# cape.net
KiCad netlist of a schematic drawn in EAGLE
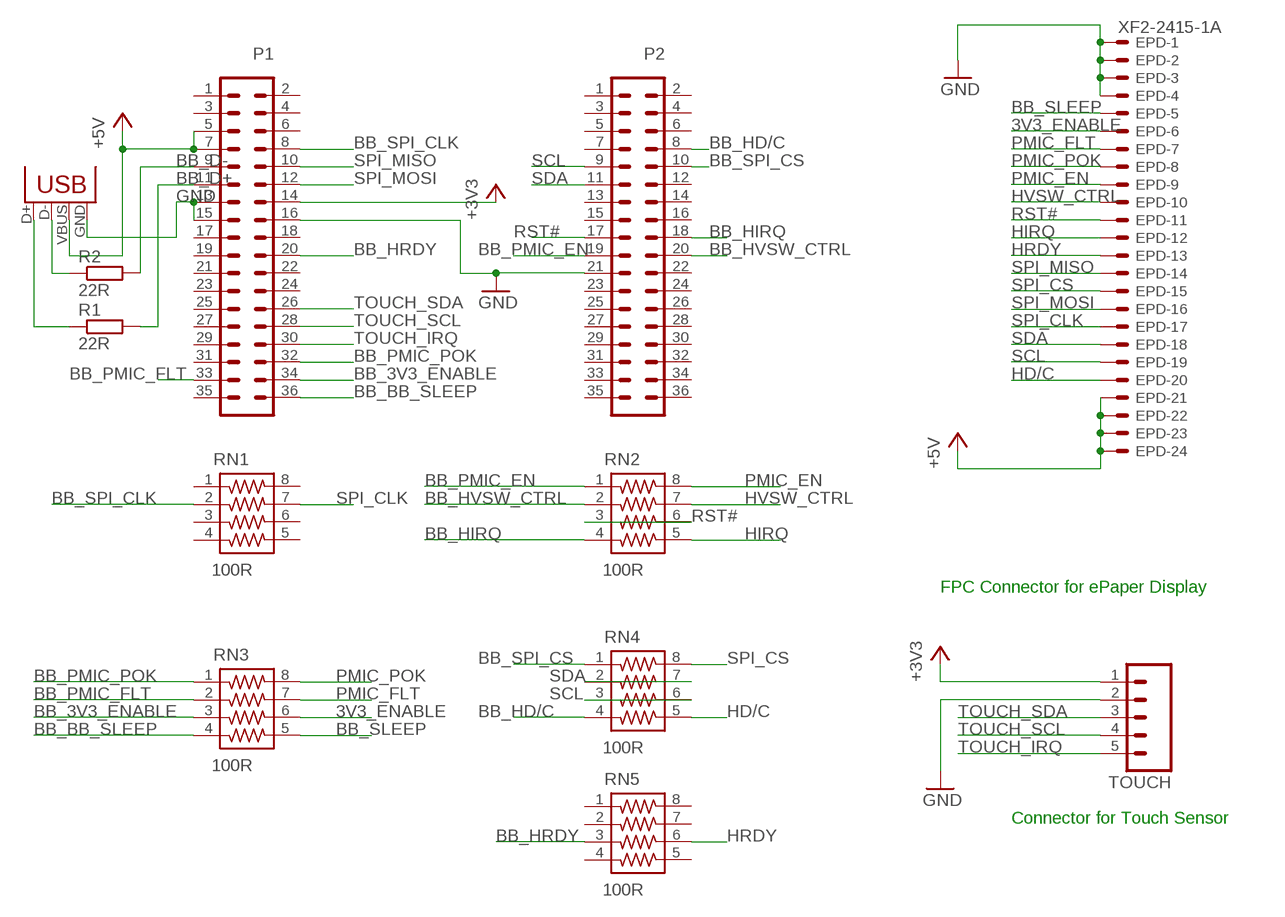
[diagram p0: schematic, sheet 1]

(export (version "E")
  (design (tool "Eeschema 10.0.6"))
  (components
    (comp (ref "EPD")
      (value "XF2-2415-1A")
      (footprint "eagle-import:XF2M-2415-1A")
      (libsource (lib "eagle-import") (part "XF2-24?15-1A"))
    )
    (comp (ref "P1")
      (value "MA18-2")
      (footprint "eagle-import:MA18-2")
      (libsource (lib "eagle-import") (part "MA18-2"))
    )
    (comp (ref "P2")
      (value "MA18-2")
      (footprint "eagle-import:MA18-2")
      (libsource (lib "eagle-import") (part "MA18-2"))
    )
    (comp (ref "R1")
      (value "22R")
      (footprint "eagle-import:R0603")
      (libsource (lib "eagle-import") (part "R-EU_R0603"))
    )
    (comp (ref "R2")
      (value "22R")
      (footprint "eagle-import:R0603")
      (libsource (lib "eagle-import") (part "R-EU_R0603"))
    )
    (comp (ref "RN1")
      (value "100R")
      (footprint "eagle-import:741-8")
      (libsource (lib "eagle-import") (part "741-8"))
    )
    (comp (ref "RN2")
      (value "100R")
      (footprint "eagle-import:741-8")
      (libsource (lib "eagle-import") (part "741-8"))
    )
    (comp (ref "RN3")
      (value "100R")
      (footprint "eagle-import:741-8")
      (libsource (lib "eagle-import") (part "741-8"))
    )
    (comp (ref "RN4")
      (value "100R")
      (footprint "eagle-import:741-8")
      (libsource (lib "eagle-import") (part "741-8"))
    )
    (comp (ref "RN5")
      (value "100R")
      (footprint "eagle-import:741-8")
      (libsource (lib "eagle-import") (part "741-8"))
    )
    (comp (ref "TOUCH")
      (value "M05PTH")
      (footprint "eagle-import:1X05")
      (libsource (lib "eagle-import") (part "M05PTH"))
    )
    (comp (ref "USB")
      (value "USB-A-H")
      (footprint "eagle-import:USB-A-H")
      (libsource (lib "eagle-import") (part "USB-A-H"))
    )
  )
  (nets
    (net (code "1") (name "+3V3") (class "Default")
      (node (ref "P1") (pin "14") (pinfunction "14_14") (pintype "passive"))
      (node (ref "TOUCH") (pin "1") (pinfunction "1_1") (pintype "passive"))
    )
    (net (code "2") (name "+5V") (class "Default")
      (node (ref "EPD") (pin "21") (pinfunction "MS_21") (pintype "passive"))
      (node (ref "EPD") (pin "22") (pinfunction "MS_22") (pintype "passive"))
      (node (ref "EPD") (pin "23") (pinfunction "MS_23") (pintype "passive"))
      (node (ref "EPD") (pin "24") (pinfunction "MS_24") (pintype "passive"))
      (node (ref "P1") (pin "5") (pinfunction "5_5") (pintype "passive"))
      (node (ref "P1") (pin "7") (pinfunction "7_7") (pintype "passive"))
      (node (ref "USB") (pin "VBUS") (pinfunction "VBUS_VBUS") (pintype "bidirectional"))
    )
    (net (code "3") (name "/3V3_ENABLE") (class "Default")
      (node (ref "EPD") (pin "6") (pinfunction "MS_6") (pintype "passive"))
      (node (ref "RN3") (pin "6") (pinfunction "6_6") (pintype "passive"))
    )
    (net (code "4") (name "/BB_3V3_ENABLE") (class "Default")
      (node (ref "P1") (pin "34") (pinfunction "34_34") (pintype "passive"))
      (node (ref "RN3") (pin "3") (pinfunction "3_3") (pintype "passive"))
    )
    (net (code "5") (name "/BB_BB_SLEEP") (class "Default")
      (node (ref "P1") (pin "36") (pinfunction "36_36") (pintype "passive"))
      (node (ref "RN3") (pin "4") (pinfunction "4_4") (pintype "passive"))
    )
    (net (code "6") (name "/BB_D+") (class "Default")
      (node (ref "P1") (pin "11") (pinfunction "11_11") (pintype "passive"))
      (node (ref "R1") (pin "2") (pinfunction "2_2") (pintype "passive"))
    )
    (net (code "7") (name "/BB_D-") (class "Default")
      (node (ref "P1") (pin "9") (pinfunction "9_9") (pintype "passive"))
      (node (ref "R2") (pin "2") (pinfunction "2_2") (pintype "passive"))
    )
    (net (code "8") (name "/BB_HD{slash}C") (class "Default")
      (node (ref "P2") (pin "8") (pinfunction "8_8") (pintype "passive"))
      (node (ref "RN4") (pin "4") (pinfunction "4_4") (pintype "passive"))
    )
    (net (code "9") (name "/BB_HIRQ") (class "Default")
      (node (ref "P2") (pin "18") (pinfunction "18_18") (pintype "passive"))
      (node (ref "RN2") (pin "4") (pinfunction "4_4") (pintype "passive"))
    )
    (net (code "10") (name "/BB_HRDY") (class "Default")
      (node (ref "P1") (pin "20") (pinfunction "20_20") (pintype "passive"))
      (node (ref "RN5") (pin "3") (pinfunction "3_3") (pintype "passive"))
    )
    (net (code "11") (name "/BB_HVSW_CTRL") (class "Default")
      (node (ref "P2") (pin "20") (pinfunction "20_20") (pintype "passive"))
      (node (ref "RN2") (pin "2") (pinfunction "2_2") (pintype "passive"))
    )
    (net (code "12") (name "/BB_PMIC_EN") (class "Default")
      (node (ref "P2") (pin "19") (pinfunction "19_19") (pintype "passive"))
      (node (ref "RN2") (pin "1") (pinfunction "1_1") (pintype "passive"))
    )
    (net (code "13") (name "/BB_PMIC_FLT") (class "Default")
      (node (ref "P1") (pin "33") (pinfunction "33_33") (pintype "passive"))
      (node (ref "RN3") (pin "2") (pinfunction "2_2") (pintype "passive"))
    )
    (net (code "14") (name "/BB_PMIC_POK") (class "Default")
      (node (ref "P1") (pin "32") (pinfunction "32_32") (pintype "passive"))
      (node (ref "RN3") (pin "1") (pinfunction "1_1") (pintype "passive"))
    )
    (net (code "15") (name "/BB_SLEEP") (class "Default")
      (node (ref "EPD") (pin "5") (pinfunction "MS_5") (pintype "passive"))
      (node (ref "RN3") (pin "5") (pinfunction "5_5") (pintype "passive"))
    )
    (net (code "16") (name "/BB_SPI_CLK") (class "Default")
      (node (ref "P1") (pin "8") (pinfunction "8_8") (pintype "passive"))
      (node (ref "RN1") (pin "2") (pinfunction "2_2") (pintype "passive"))
    )
    (net (code "17") (name "/BB_SPI_CS") (class "Default")
      (node (ref "P2") (pin "10") (pinfunction "10_10") (pintype "passive"))
      (node (ref "RN4") (pin "1") (pinfunction "1_1") (pintype "passive"))
    )
    (net (code "18") (name "/HD{slash}C") (class "Default")
      (node (ref "EPD") (pin "20") (pinfunction "MS_20") (pintype "passive"))
      (node (ref "RN4") (pin "5") (pinfunction "5_5") (pintype "passive"))
    )
    (net (code "19") (name "/HIRQ") (class "Default")
      (node (ref "EPD") (pin "12") (pinfunction "MS_12") (pintype "passive"))
      (node (ref "RN2") (pin "5") (pinfunction "5_5") (pintype "passive"))
    )
    (net (code "20") (name "/HRDY") (class "Default")
      (node (ref "EPD") (pin "13") (pinfunction "MS_13") (pintype "passive"))
      (node (ref "RN5") (pin "6") (pinfunction "6_6") (pintype "passive"))
    )
    (net (code "21") (name "/HVSW_CTRL") (class "Default")
      (node (ref "EPD") (pin "10") (pinfunction "MS_10") (pintype "passive"))
      (node (ref "RN2") (pin "7") (pinfunction "7_7") (pintype "passive"))
    )
    (net (code "22") (name "/PMIC_EN") (class "Default")
      (node (ref "EPD") (pin "9") (pinfunction "MS_9") (pintype "passive"))
      (node (ref "RN2") (pin "8") (pinfunction "8_8") (pintype "passive"))
    )
    (net (code "23") (name "/PMIC_FLT") (class "Default")
      (node (ref "EPD") (pin "7") (pinfunction "MS_7") (pintype "passive"))
      (node (ref "RN3") (pin "7") (pinfunction "7_7") (pintype "passive"))
    )
    (net (code "24") (name "/PMIC_POK") (class "Default")
      (node (ref "EPD") (pin "8") (pinfunction "MS_8") (pintype "passive"))
      (node (ref "RN3") (pin "8") (pinfunction "8_8") (pintype "passive"))
    )
    (net (code "25") (name "/RST#") (class "Default")
      (node (ref "EPD") (pin "11") (pinfunction "MS_11") (pintype "passive"))
      (node (ref "P2") (pin "17") (pinfunction "17_17") (pintype "passive"))
      (node (ref "RN2") (pin "3") (pinfunction "3_3") (pintype "passive"))
      (node (ref "RN2") (pin "6") (pinfunction "6_6") (pintype "passive"))
    )
    (net (code "26") (name "/SCL") (class "Default")
      (node (ref "EPD") (pin "19") (pinfunction "MS_19") (pintype "passive"))
      (node (ref "P2") (pin "9") (pinfunction "9_9") (pintype "passive"))
      (node (ref "RN4") (pin "3") (pinfunction "3_3") (pintype "passive"))
      (node (ref "RN4") (pin "6") (pinfunction "6_6") (pintype "passive"))
    )
    (net (code "27") (name "/SDA") (class "Default")
      (node (ref "EPD") (pin "18") (pinfunction "MS_18") (pintype "passive"))
      (node (ref "P2") (pin "11") (pinfunction "11_11") (pintype "passive"))
      (node (ref "RN4") (pin "2") (pinfunction "2_2") (pintype "passive"))
      (node (ref "RN4") (pin "7") (pinfunction "7_7") (pintype "passive"))
    )
    (net (code "28") (name "/SPI_CLK") (class "Default")
      (node (ref "EPD") (pin "17") (pinfunction "MS_17") (pintype "passive"))
      (node (ref "RN1") (pin "7") (pinfunction "7_7") (pintype "passive"))
    )
    (net (code "29") (name "/SPI_CS") (class "Default")
      (node (ref "EPD") (pin "15") (pinfunction "MS_15") (pintype "passive"))
      (node (ref "RN4") (pin "8") (pinfunction "8_8") (pintype "passive"))
    )
    (net (code "30") (name "/SPI_MISO") (class "Default")
      (node (ref "EPD") (pin "14") (pinfunction "MS_14") (pintype "passive"))
      (node (ref "P1") (pin "10") (pinfunction "10_10") (pintype "passive"))
    )
    (net (code "31") (name "/SPI_MOSI") (class "Default")
      (node (ref "EPD") (pin "16") (pinfunction "MS_16") (pintype "passive"))
      (node (ref "P1") (pin "12") (pinfunction "12_12") (pintype "passive"))
    )
    (net (code "32") (name "/TOUCH_IRQ") (class "Default")
      (node (ref "P1") (pin "30") (pinfunction "30_30") (pintype "passive"))
      (node (ref "TOUCH") (pin "5") (pinfunction "5_5") (pintype "passive"))
    )
    (net (code "33") (name "/TOUCH_SCL") (class "Default")
      (node (ref "P1") (pin "28") (pinfunction "28_28") (pintype "passive"))
      (node (ref "TOUCH") (pin "4") (pinfunction "4_4") (pintype "passive"))
    )
    (net (code "34") (name "/TOUCH_SDA") (class "Default")
      (node (ref "P1") (pin "26") (pinfunction "26_26") (pintype "passive"))
      (node (ref "TOUCH") (pin "3") (pinfunction "3_3") (pintype "passive"))
    )
    (net (code "35") (name "GND") (class "Default")
      (node (ref "EPD") (pin "1") (pinfunction "MSV_1") (pintype "passive"))
      (node (ref "EPD") (pin "2") (pinfunction "MS_2") (pintype "passive"))
      (node (ref "EPD") (pin "3") (pinfunction "MS_3") (pintype "passive"))
      (node (ref "EPD") (pin "4") (pinfunction "MS_4") (pintype "passive"))
      (node (ref "P1") (pin "13") (pinfunction "13_13") (pintype "passive"))
      (node (ref "P1") (pin "15") (pinfunction "15_15") (pintype "passive"))
      (node (ref "P1") (pin "16") (pinfunction "16_16") (pintype "passive"))
      (node (ref "P2") (pin "21") (pinfunction "21_21") (pintype "passive"))
      (node (ref "TOUCH") (pin "2") (pinfunction "2_2") (pintype "passive"))
      (node (ref "USB") (pin "GND") (pinfunction "GND_GND") (pintype "bidirectional"))
    )
    (net (code "36") (name "Net-(R1-Pad1)") (class "Default")
      (node (ref "R1") (pin "1") (pinfunction "1_1") (pintype "passive"))
      (node (ref "USB") (pin "D+") (pinfunction "D+_D+") (pintype "bidirectional"))
    )
    (net (code "37") (name "Net-(R2-Pad1)") (class "Default")
      (node (ref "R2") (pin "1") (pinfunction "1_1") (pintype "passive"))
      (node (ref "USB") (pin "D-") (pinfunction "D-_D-") (pintype "bidirectional"))
    )
    (net (code "38") (name "unconnected-(P1-Pad1)") (class "Default")
      (node (ref "P1") (pin "1") (pinfunction "1_1") (pintype "passive"))
    )
    (net (code "39") (name "unconnected-(P1-Pad2)") (class "Default")
      (node (ref "P1") (pin "2") (pinfunction "2_2") (pintype "passive"))
    )
    (net (code "40") (name "unconnected-(P1-Pad3)") (class "Default")
      (node (ref "P1") (pin "3") (pinfunction "3_3") (pintype "passive"))
    )
    (net (code "41") (name "unconnected-(P1-Pad4)") (class "Default")
      (node (ref "P1") (pin "4") (pinfunction "4_4") (pintype "passive"))
    )
    (net (code "42") (name "unconnected-(P1-Pad6)") (class "Default")
      (node (ref "P1") (pin "6") (pinfunction "6_6") (pintype "passive"))
    )
    (net (code "43") (name "unconnected-(P1-Pad17)") (class "Default")
      (node (ref "P1") (pin "17") (pinfunction "17_17") (pintype "passive"))
    )
    (net (code "44") (name "unconnected-(P1-Pad18)") (class "Default")
      (node (ref "P1") (pin "18") (pinfunction "18_18") (pintype "passive"))
    )
    (net (code "45") (name "unconnected-(P1-Pad19)") (class "Default")
      (node (ref "P1") (pin "19") (pinfunction "19_19") (pintype "passive"))
    )
    (net (code "46") (name "unconnected-(P1-Pad21)") (class "Default")
      (node (ref "P1") (pin "21") (pinfunction "21_21") (pintype "passive"))
    )
    (net (code "47") (name "unconnected-(P1-Pad22)") (class "Default")
      (node (ref "P1") (pin "22") (pinfunction "22_22") (pintype "passive"))
    )
    (net (code "48") (name "unconnected-(P1-Pad23)") (class "Default")
      (node (ref "P1") (pin "23") (pinfunction "23_23") (pintype "passive"))
    )
    (net (code "49") (name "unconnected-(P1-Pad24)") (class "Default")
      (node (ref "P1") (pin "24") (pinfunction "24_24") (pintype "passive"))
    )
    (net (code "50") (name "unconnected-(P1-Pad25)") (class "Default")
      (node (ref "P1") (pin "25") (pinfunction "25_25") (pintype "passive"))
    )
    (net (code "51") (name "unconnected-(P1-Pad27)") (class "Default")
      (node (ref "P1") (pin "27") (pinfunction "27_27") (pintype "passive"))
    )
    (net (code "52") (name "unconnected-(P1-Pad29)") (class "Default")
      (node (ref "P1") (pin "29") (pinfunction "29_29") (pintype "passive"))
    )
    (net (code "53") (name "unconnected-(P1-Pad31)") (class "Default")
      (node (ref "P1") (pin "31") (pinfunction "31_31") (pintype "passive"))
    )
    (net (code "54") (name "unconnected-(P1-Pad35)") (class "Default")
      (node (ref "P1") (pin "35") (pinfunction "35_35") (pintype "passive"))
    )
    (net (code "55") (name "unconnected-(P2-Pad1)") (class "Default")
      (node (ref "P2") (pin "1") (pinfunction "1_1") (pintype "passive"))
    )
    (net (code "56") (name "unconnected-(P2-Pad2)") (class "Default")
      (node (ref "P2") (pin "2") (pinfunction "2_2") (pintype "passive"))
    )
    (net (code "57") (name "unconnected-(P2-Pad3)") (class "Default")
      (node (ref "P2") (pin "3") (pinfunction "3_3") (pintype "passive"))
    )
    (net (code "58") (name "unconnected-(P2-Pad4)") (class "Default")
      (node (ref "P2") (pin "4") (pinfunction "4_4") (pintype "passive"))
    )
    (net (code "59") (name "unconnected-(P2-Pad5)") (class "Default")
      (node (ref "P2") (pin "5") (pinfunction "5_5") (pintype "passive"))
    )
    (net (code "60") (name "unconnected-(P2-Pad6)") (class "Default")
      (node (ref "P2") (pin "6") (pinfunction "6_6") (pintype "passive"))
    )
    (net (code "61") (name "unconnected-(P2-Pad7)") (class "Default")
      (node (ref "P2") (pin "7") (pinfunction "7_7") (pintype "passive"))
    )
    (net (code "62") (name "unconnected-(P2-Pad12)") (class "Default")
      (node (ref "P2") (pin "12") (pinfunction "12_12") (pintype "passive"))
    )
    (net (code "63") (name "unconnected-(P2-Pad13)") (class "Default")
      (node (ref "P2") (pin "13") (pinfunction "13_13") (pintype "passive"))
    )
    (net (code "64") (name "unconnected-(P2-Pad14)") (class "Default")
      (node (ref "P2") (pin "14") (pinfunction "14_14") (pintype "passive"))
    )
    (net (code "65") (name "unconnected-(P2-Pad15)") (class "Default")
      (node (ref "P2") (pin "15") (pinfunction "15_15") (pintype "passive"))
    )
    (net (code "66") (name "unconnected-(P2-Pad16)") (class "Default")
      (node (ref "P2") (pin "16") (pinfunction "16_16") (pintype "passive"))
    )
    (net (code "67") (name "unconnected-(P2-Pad22)") (class "Default")
      (node (ref "P2") (pin "22") (pinfunction "22_22") (pintype "passive"))
    )
    (net (code "68") (name "unconnected-(P2-Pad23)") (class "Default")
      (node (ref "P2") (pin "23") (pinfunction "23_23") (pintype "passive"))
    )
    (net (code "69") (name "unconnected-(P2-Pad24)") (class "Default")
      (node (ref "P2") (pin "24") (pinfunction "24_24") (pintype "passive"))
    )
    (net (code "70") (name "unconnected-(P2-Pad25)") (class "Default")
      (node (ref "P2") (pin "25") (pinfunction "25_25") (pintype "passive"))
    )
    (net (code "71") (name "unconnected-(P2-Pad26)") (class "Default")
      (node (ref "P2") (pin "26") (pinfunction "26_26") (pintype "passive"))
    )
    (net (code "72") (name "unconnected-(P2-Pad27)") (class "Default")
      (node (ref "P2") (pin "27") (pinfunction "27_27") (pintype "passive"))
    )
    (net (code "73") (name "unconnected-(P2-Pad28)") (class "Default")
      (node (ref "P2") (pin "28") (pinfunction "28_28") (pintype "passive"))
    )
    (net (code "74") (name "unconnected-(P2-Pad29)") (class "Default")
      (node (ref "P2") (pin "29") (pinfunction "29_29") (pintype "passive"))
    )
    (net (code "75") (name "unconnected-(P2-Pad30)") (class "Default")
      (node (ref "P2") (pin "30") (pinfunction "30_30") (pintype "passive"))
    )
    (net (code "76") (name "unconnected-(P2-Pad31)") (class "Default")
      (node (ref "P2") (pin "31") (pinfunction "31_31") (pintype "passive"))
    )
    (net (code "77") (name "unconnected-(P2-Pad32)") (class "Default")
      (node (ref "P2") (pin "32") (pinfunction "32_32") (pintype "passive"))
    )
    (net (code "78") (name "unconnected-(P2-Pad33)") (class "Default")
      (node (ref "P2") (pin "33") (pinfunction "33_33") (pintype "passive"))
    )
    (net (code "79") (name "unconnected-(P2-Pad34)") (class "Default")
      (node (ref "P2") (pin "34") (pinfunction "34_34") (pintype "passive"))
    )
    (net (code "80") (name "unconnected-(P2-Pad35)") (class "Default")
      (node (ref "P2") (pin "35") (pinfunction "35_35") (pintype "passive"))
    )
    (net (code "81") (name "unconnected-(P2-Pad36)") (class "Default")
      (node (ref "P2") (pin "36") (pinfunction "36_36") (pintype "passive"))
    )
    (net (code "82") (name "unconnected-(RN1-Pad1)") (class "Default")
      (node (ref "RN1") (pin "1") (pinfunction "1_1") (pintype "passive"))
    )
    (net (code "83") (name "unconnected-(RN1-Pad3)") (class "Default")
      (node (ref "RN1") (pin "3") (pinfunction "3_3") (pintype "passive"))
    )
    (net (code "84") (name "unconnected-(RN1-Pad4)") (class "Default")
      (node (ref "RN1") (pin "4") (pinfunction "4_4") (pintype "passive"))
    )
    (net (code "85") (name "unconnected-(RN1-Pad5)") (class "Default")
      (node (ref "RN1") (pin "5") (pinfunction "5_5") (pintype "passive"))
    )
    (net (code "86") (name "unconnected-(RN1-Pad6)") (class "Default")
      (node (ref "RN1") (pin "6") (pinfunction "6_6") (pintype "passive"))
    )
    (net (code "87") (name "unconnected-(RN1-Pad8)") (class "Default")
      (node (ref "RN1") (pin "8") (pinfunction "8_8") (pintype "passive"))
    )
    (net (code "88") (name "unconnected-(RN5-Pad1)") (class "Default")
      (node (ref "RN5") (pin "1") (pinfunction "1_1") (pintype "passive"))
    )
    (net (code "89") (name "unconnected-(RN5-Pad2)") (class "Default")
      (node (ref "RN5") (pin "2") (pinfunction "2_2") (pintype "passive"))
    )
    (net (code "90") (name "unconnected-(RN5-Pad4)") (class "Default")
      (node (ref "RN5") (pin "4") (pinfunction "4_4") (pintype "passive"))
    )
    (net (code "91") (name "unconnected-(RN5-Pad5)") (class "Default")
      (node (ref "RN5") (pin "5") (pinfunction "5_5") (pintype "passive"))
    )
    (net (code "92") (name "unconnected-(RN5-Pad7)") (class "Default")
      (node (ref "RN5") (pin "7") (pinfunction "7_7") (pintype "passive"))
    )
    (net (code "93") (name "unconnected-(RN5-Pad8)") (class "Default")
      (node (ref "RN5") (pin "8") (pinfunction "8_8") (pintype "passive"))
    )
  )
)
